# filmprocessor.net
KiCad netlist of a schematic drawn in EasyEDA Pro
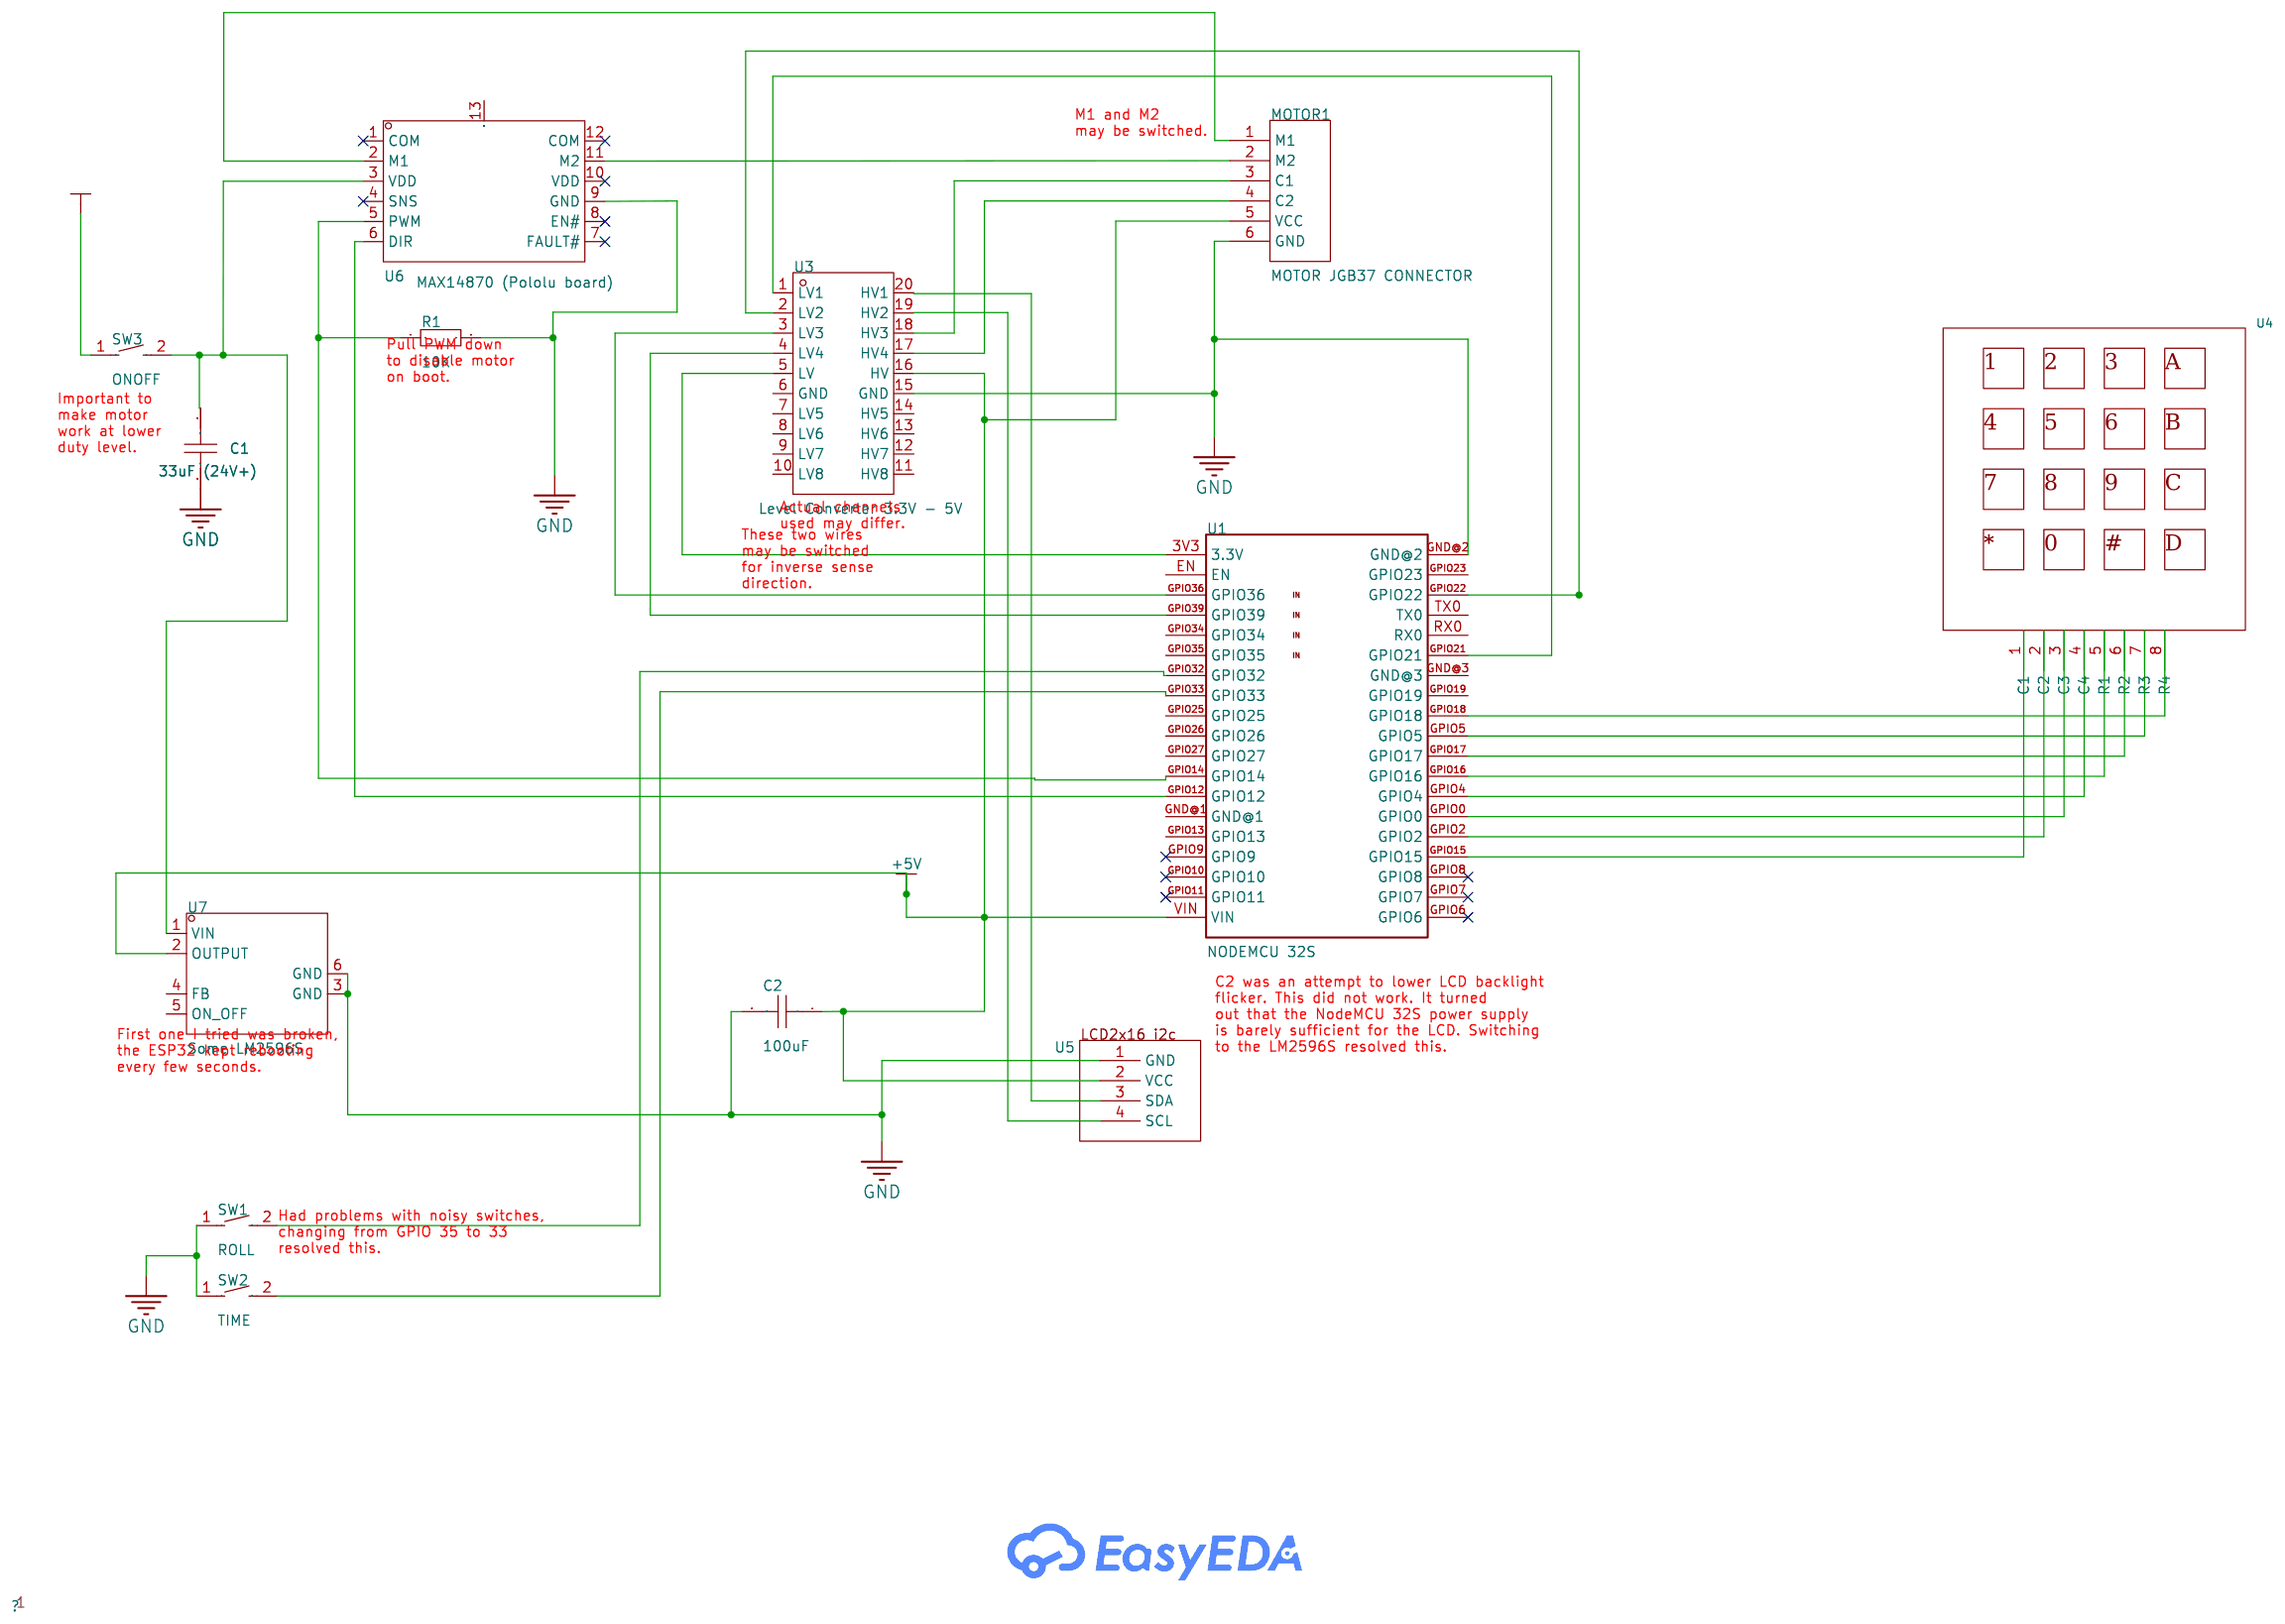
[diagram p0: schematic sheet]

(export (version "E")
  (design (tool "Eeschema 10.0.6"))
  (components
    (comp (ref "C1")
      (value "33uF (24V+)")
      (footprint "easyedapro:C0603")
      (libsource (lib "easyedapro") (part "CAP"))
    )
    (comp (ref "C2")
      (value "100uF")
      (footprint "easyedapro:C0603")
      (libsource (lib "easyedapro") (part "CAP"))
    )
    (comp (ref "MOTOR1")
      (value "MOTOR JGB37 CONNECTOR")
      (libsource (lib "easyedapro") (part "MOTOR JGB37 CONNECTOR"))
    )
    (comp (ref "R1") (value "10K") (footprint "easyedapro:R0603") (libsource (lib "easyedapro") (part "Res")))
    (comp (ref "SW1")
      (value "ROLL")
      (footprint "easyedapro:KEY-SMD_L6.0-W3.5-LS8.0")
      (libsource (lib "easyedapro") (part "BUTTON2,KEY"))
    )
    (comp (ref "SW2")
      (value "TIME")
      (footprint "easyedapro:KEY-SMD_L6.0-W3.5-LS8.0")
      (libsource (lib "easyedapro") (part "BUTTON2,KEY"))
    )
    (comp (ref "SW3")
      (value "ONOFF")
      (footprint "easyedapro:KEY-SMD_L6.0-W3.5-LS8.0")
      (libsource (lib "easyedapro") (part "BUTTON2,KEY"))
    )
    (comp (ref "U1")
      (value "NODEMCU32S")
      (footprint "easyedapro:footprints:NODEMCU32S")
      (libsource (lib "easyedapro") (part "NODEMCU32S_NODEMCU32S"))
    )
    (comp (ref "U3")
      (value "Level Converter 3.3V - 5V")
      (footprint "easyedapro:MPN-TH-20_L28.0-W14.0-P2.54-BL")
      (libsource (lib "easyedapro") (part "LEVEL CONVERTER 8"))
    )
    (comp (ref "U4") (value "~") (libsource (lib "easyedapro") (part "keypad")))
    (comp (ref "U5") (value "~") (libsource (lib "easyedapro") (part "lcd_2x16 with i2c module")))
    (comp (ref "U6")
      (value "MAX14870 (Pololu board)")
      (footprint "easyedapro:DFN-12_L3.0-W3.0-P0.50-LS3.0-BL-EP")
      (fields (field (name "Manufacturer") "ADI(亚德诺)/MAXIM(美信)"))
      (libsource (lib "easyedapro") (part "MAX14870ETC+T"))
    )
    (comp (ref "U7")
      (value "Some LM2596S")
      (footprint "easyedapro:TO-263-5_L10.4-W8.6-P1.70-LS15.3-BR")
      (libsource (lib "easyedapro") (part "LM2596S-ADJ_C3198435"))
    )
  )
  (nets
    (net (code "1") (name "+5V") (class "Default")
      (node (ref "C2") (pin "1") (pinfunction "1_1") (pintype "input"))
      (node (ref "MOTOR1") (pin "5") (pinfunction "VCC_5") (pintype "unspecified"))
      (node (ref "U1") (pin "VIN") (pinfunction "VIN_VIN") (pintype "bidirectional"))
      (node (ref "U3") (pin "16") (pinfunction "HV_16") (pintype "input"))
      (node (ref "U5") (pin "2") (pinfunction "VCC_2") (pintype "input"))
      (node (ref "U7") (pin "2") (pinfunction "OUTPUT_2") (pintype "unspecified"))
    )
    (net (code "2") (name "+24V") (class "Default")
      (node (ref "SW3") (pin "1") (pinfunction "1_1") (pintype "unspecified"))
    )
    (net (code "3") (name "GND") (class "Default")
      (node (ref "C1") (pin "2") (pinfunction "2_2") (pintype "input"))
      (node (ref "C2") (pin "2") (pinfunction "2_2") (pintype "input"))
      (node (ref "MOTOR1") (pin "6") (pinfunction "GND_6") (pintype "unspecified"))
      (node (ref "R1") (pin "2") (pinfunction "2_2") (pintype "input"))
      (node (ref "SW1") (pin "1") (pinfunction "1_1") (pintype "unspecified"))
      (node (ref "SW2") (pin "1") (pinfunction "1_1") (pintype "unspecified"))
      (node (ref "U1") (pin "GND@2") (pinfunction "GND@2_GND@2") (pintype "bidirectional"))
      (node (ref "U3") (pin "15") (pinfunction "GND_15") (pintype "input"))
      (node (ref "U5") (pin "1") (pinfunction "GND_1") (pintype "input"))
      (node (ref "U6") (pin "9") (pinfunction "GND_9") (pintype "unspecified"))
      (node (ref "U7") (pin "3") (pinfunction "GND_3") (pintype "unspecified"))
      (node (ref "U7") (pin "6") (pinfunction "GND_6") (pintype "unspecified"))
    )
    (net (code "4") (name "Net-(MOTOR1-C1)") (class "Default")
      (node (ref "MOTOR1") (pin "3") (pinfunction "C1_3") (pintype "unspecified"))
      (node (ref "U3") (pin "18") (pinfunction "HV3_18") (pintype "input"))
    )
    (net (code "5") (name "Net-(MOTOR1-C2)") (class "Default")
      (node (ref "MOTOR1") (pin "4") (pinfunction "C2_4") (pintype "unspecified"))
      (node (ref "U3") (pin "17") (pinfunction "HV4_17") (pintype "input"))
    )
    (net (code "6") (name "Net-(MOTOR1-M1)") (class "Default")
      (node (ref "MOTOR1") (pin "1") (pinfunction "M1_1") (pintype "unspecified"))
      (node (ref "U6") (pin "2") (pinfunction "M1_2") (pintype "unspecified"))
    )
    (net (code "7") (name "Net-(MOTOR1-M2)") (class "Default")
      (node (ref "MOTOR1") (pin "2") (pinfunction "M2_2") (pintype "unspecified"))
      (node (ref "U6") (pin "11") (pinfunction "M2_11") (pintype "unspecified"))
    )
    (net (code "8") (name "Net-(SW1-Pad2)") (class "Default")
      (node (ref "SW1") (pin "2") (pinfunction "2_2") (pintype "unspecified"))
      (node (ref "U1") (pin "GPIO32") (pinfunction "GPIO32_GPIO32") (pintype "bidirectional"))
    )
    (net (code "9") (name "Net-(SW2-Pad2)") (class "Default")
      (node (ref "SW2") (pin "2") (pinfunction "2_2") (pintype "unspecified"))
      (node (ref "U1") (pin "GPIO33") (pinfunction "GPIO33_GPIO33") (pintype "bidirectional"))
    )
    (net (code "10") (name "Net-(U1-3.3V)") (class "Default")
      (node (ref "U1") (pin "3V3") (pinfunction "3.3V_3V3") (pintype "bidirectional"))
      (node (ref "U3") (pin "5") (pinfunction "LV_5") (pintype "input"))
    )
    (net (code "11") (name "Net-(U3-HV1)") (class "Default")
      (node (ref "U3") (pin "20") (pinfunction "HV1_20") (pintype "input"))
      (node (ref "U5") (pin "3") (pinfunction "SDA_3") (pintype "input"))
    )
    (net (code "12") (name "Net-(U3-LV1)") (class "Default")
      (node (ref "U1") (pin "GPIO21") (pinfunction "GPIO21_GPIO21") (pintype "bidirectional"))
      (node (ref "U3") (pin "1") (pinfunction "LV1_1") (pintype "input"))
    )
    (net (code "13") (name "Net-(U3-LV2)") (class "Default")
      (node (ref "U1") (pin "GPIO22") (pinfunction "GPIO22_GPIO22") (pintype "bidirectional"))
      (node (ref "U3") (pin "2") (pinfunction "LV2_2") (pintype "input"))
    )
    (net (code "14") (name "Net-(U3-LV3)") (class "Default")
      (node (ref "U1") (pin "GPIO36") (pinfunction "GPIO36_GPIO36") (pintype "input"))
      (node (ref "U3") (pin "3") (pinfunction "LV3_3") (pintype "input"))
    )
    (net (code "15") (name "Net-(U3-LV4)") (class "Default")
      (node (ref "U1") (pin "GPIO39") (pinfunction "GPIO39_GPIO39") (pintype "input"))
      (node (ref "U3") (pin "4") (pinfunction "LV4_4") (pintype "input"))
    )
    (net (code "16") (name "Net-(U4-C1)") (class "Default")
      (node (ref "U1") (pin "GPIO15") (pinfunction "GPIO15_GPIO15") (pintype "bidirectional"))
      (node (ref "U4") (pin "1") (pinfunction "C1_1") (pintype "input"))
    )
    (net (code "17") (name "Net-(U4-C2)") (class "Default")
      (node (ref "U1") (pin "GPIO2") (pinfunction "GPIO2_GPIO2") (pintype "bidirectional"))
      (node (ref "U4") (pin "2") (pinfunction "C2_2") (pintype "input"))
    )
    (net (code "18") (name "Net-(U4-C3)") (class "Default")
      (node (ref "U1") (pin "GPIO0") (pinfunction "GPIO0_GPIO0") (pintype "bidirectional"))
      (node (ref "U4") (pin "3") (pinfunction "C3_3") (pintype "input"))
    )
    (net (code "19") (name "Net-(U4-C4)") (class "Default")
      (node (ref "U1") (pin "GPIO4") (pinfunction "GPIO4_GPIO4") (pintype "bidirectional"))
      (node (ref "U4") (pin "4") (pinfunction "C4_4") (pintype "input"))
    )
    (net (code "20") (name "Net-(U4-R1)") (class "Default")
      (node (ref "U1") (pin "GPIO16") (pinfunction "GPIO16_GPIO16") (pintype "bidirectional"))
      (node (ref "U4") (pin "5") (pinfunction "R1_5") (pintype "input"))
    )
    (net (code "21") (name "Net-(U4-R2)") (class "Default")
      (node (ref "U1") (pin "GPIO17") (pinfunction "GPIO17_GPIO17") (pintype "bidirectional"))
      (node (ref "U4") (pin "6") (pinfunction "R2_6") (pintype "input"))
    )
    (net (code "22") (name "Net-(U4-R3)") (class "Default")
      (node (ref "U1") (pin "GPIO5") (pinfunction "GPIO5_GPIO5") (pintype "bidirectional"))
      (node (ref "U4") (pin "7") (pinfunction "R3_7") (pintype "input"))
    )
    (net (code "23") (name "Net-(U4-R4)") (class "Default")
      (node (ref "U1") (pin "GPIO18") (pinfunction "GPIO18_GPIO18") (pintype "bidirectional"))
      (node (ref "U4") (pin "8") (pinfunction "R4_8") (pintype "input"))
    )
    (net (code "24") (name "Net-(U6-DIR)") (class "Default")
      (node (ref "U1") (pin "GPIO12") (pinfunction "GPIO12_GPIO12") (pintype "bidirectional"))
      (node (ref "U6") (pin "6") (pinfunction "DIR_6") (pintype "unspecified"))
    )
    (net (code "25") (name "Net-(U6-PWM)") (class "Default")
      (node (ref "R1") (pin "1") (pinfunction "1_1") (pintype "input"))
      (node (ref "U1") (pin "GPIO14") (pinfunction "GPIO14_GPIO14") (pintype "bidirectional"))
      (node (ref "U6") (pin "5") (pinfunction "PWM_5") (pintype "unspecified"))
    )
    (net (code "26") (name "Net-(U7-VIN)") (class "Default")
      (node (ref "C1") (pin "1") (pinfunction "1_1") (pintype "input"))
      (node (ref "SW3") (pin "2") (pinfunction "2_2") (pintype "unspecified"))
      (node (ref "U6") (pin "3") (pinfunction "VDD_3") (pintype "unspecified"))
      (node (ref "U7") (pin "1") (pinfunction "VIN_1") (pintype "unspecified"))
    )
    (net (code "27") (name "unconnected-(U1-PadEN)") (class "Default")
      (node (ref "U1") (pin "EN") (pinfunction "EN_EN") (pintype "bidirectional"))
    )
    (net (code "28") (name "unconnected-(U1-PadGND@1)") (class "Default")
      (node (ref "U1") (pin "GND@1") (pinfunction "GND@1_GND@1") (pintype "bidirectional"))
    )
    (net (code "29") (name "unconnected-(U1-PadGND@3)") (class "Default")
      (node (ref "U1") (pin "GND@3") (pinfunction "GND@3_GND@3") (pintype "bidirectional"))
    )
    (net (code "30") (name "unconnected-(U1-PadGPIO6)") (class "Default")
      (node (ref "U1") (pin "GPIO6") (pinfunction "GPIO6_GPIO6") (pintype "bidirectional+no_connect"))
    )
    (net (code "31") (name "unconnected-(U1-PadGPIO7)") (class "Default")
      (node (ref "U1") (pin "GPIO7") (pinfunction "GPIO7_GPIO7") (pintype "bidirectional+no_connect"))
    )
    (net (code "32") (name "unconnected-(U1-PadGPIO8)") (class "Default")
      (node (ref "U1") (pin "GPIO8") (pinfunction "GPIO8_GPIO8") (pintype "bidirectional+no_connect"))
    )
    (net (code "33") (name "unconnected-(U1-PadGPIO9)") (class "Default")
      (node (ref "U1") (pin "GPIO9") (pinfunction "GPIO9_GPIO9") (pintype "bidirectional+no_connect"))
    )
    (net (code "34") (name "unconnected-(U1-PadGPIO10)") (class "Default")
      (node (ref "U1") (pin "GPIO10") (pinfunction "GPIO10_GPIO10") (pintype "bidirectional+no_connect"))
    )
    (net (code "35") (name "unconnected-(U1-PadGPIO11)") (class "Default")
      (node (ref "U1") (pin "GPIO11") (pinfunction "GPIO11_GPIO11") (pintype "bidirectional+no_connect"))
    )
    (net (code "36") (name "unconnected-(U1-PadGPIO13)") (class "Default")
      (node (ref "U1") (pin "GPIO13") (pinfunction "GPIO13_GPIO13") (pintype "bidirectional"))
    )
    (net (code "37") (name "unconnected-(U1-PadGPIO19)") (class "Default")
      (node (ref "U1") (pin "GPIO19") (pinfunction "GPIO19_GPIO19") (pintype "bidirectional"))
    )
    (net (code "38") (name "unconnected-(U1-PadGPIO23)") (class "Default")
      (node (ref "U1") (pin "GPIO23") (pinfunction "GPIO23_GPIO23") (pintype "bidirectional"))
    )
    (net (code "39") (name "unconnected-(U1-PadGPIO25)") (class "Default")
      (node (ref "U1") (pin "GPIO25") (pinfunction "GPIO25_GPIO25") (pintype "bidirectional"))
    )
    (net (code "40") (name "unconnected-(U1-PadGPIO26)") (class "Default")
      (node (ref "U1") (pin "GPIO26") (pinfunction "GPIO26_GPIO26") (pintype "bidirectional"))
    )
    (net (code "41") (name "unconnected-(U1-PadGPIO27)") (class "Default")
      (node (ref "U1") (pin "GPIO27") (pinfunction "GPIO27_GPIO27") (pintype "bidirectional"))
    )
    (net (code "42") (name "unconnected-(U1-PadGPIO34)") (class "Default")
      (node (ref "U1") (pin "GPIO34") (pinfunction "GPIO34_GPIO34") (pintype "input"))
    )
    (net (code "43") (name "unconnected-(U1-PadGPIO35)") (class "Default")
      (node (ref "U1") (pin "GPIO35") (pinfunction "GPIO35_GPIO35") (pintype "input"))
    )
    (net (code "44") (name "unconnected-(U1-PadRX0)") (class "Default")
      (node (ref "U1") (pin "RX0") (pinfunction "RX0_RX0") (pintype "bidirectional"))
    )
    (net (code "45") (name "unconnected-(U1-PadTX0)") (class "Default")
      (node (ref "U1") (pin "TX0") (pinfunction "TX0_TX0") (pintype "bidirectional"))
    )
    (net (code "46") (name "unconnected-(U3-GND-Pad6)") (class "Default")
      (node (ref "U3") (pin "6") (pinfunction "GND_6") (pintype "input"))
    )
    (net (code "47") (name "unconnected-(U3-HV2-Pad19)") (class "Default")
      (node (ref "U3") (pin "19") (pinfunction "HV2_19") (pintype "input"))
    )
    (net (code "48") (name "unconnected-(U3-HV5-Pad14)") (class "Default")
      (node (ref "U3") (pin "14") (pinfunction "HV5_14") (pintype "input"))
    )
    (net (code "49") (name "unconnected-(U3-HV6-Pad13)") (class "Default")
      (node (ref "U3") (pin "13") (pinfunction "HV6_13") (pintype "input"))
    )
    (net (code "50") (name "unconnected-(U3-HV7-Pad12)") (class "Default")
      (node (ref "U3") (pin "12") (pinfunction "HV7_12") (pintype "input"))
    )
    (net (code "51") (name "unconnected-(U3-HV8-Pad11)") (class "Default")
      (node (ref "U3") (pin "11") (pinfunction "HV8_11") (pintype "input"))
    )
    (net (code "52") (name "unconnected-(U3-LV5-Pad7)") (class "Default")
      (node (ref "U3") (pin "7") (pinfunction "LV5_7") (pintype "input"))
    )
    (net (code "53") (name "unconnected-(U3-LV6-Pad8)") (class "Default")
      (node (ref "U3") (pin "8") (pinfunction "LV6_8") (pintype "input"))
    )
    (net (code "54") (name "unconnected-(U3-LV7-Pad9)") (class "Default")
      (node (ref "U3") (pin "9") (pinfunction "LV7_9") (pintype "input"))
    )
    (net (code "55") (name "unconnected-(U3-LV8-Pad10)") (class "Default")
      (node (ref "U3") (pin "10") (pinfunction "LV8_10") (pintype "input"))
    )
    (net (code "56") (name "unconnected-(U5-SCL-Pad4)") (class "Default")
      (node (ref "U5") (pin "4") (pinfunction "SCL_4") (pintype "input"))
    )
    (net (code "57") (name "unconnected-(U6-COM-Pad1)") (class "Default")
      (node (ref "U6") (pin "1") (pinfunction "COM_1") (pintype "unspecified+no_connect"))
    )
    (net (code "58") (name "unconnected-(U6-COM-Pad12)") (class "Default")
      (node (ref "U6") (pin "12") (pinfunction "COM_12") (pintype "unspecified+no_connect"))
    )
    (net (code "59") (name "unconnected-(U6-EN#-Pad8)") (class "Default")
      (node (ref "U6") (pin "8") (pinfunction "EN#_8") (pintype "unspecified+no_connect"))
    )
    (net (code "60") (name "unconnected-(U6-FAULT#-Pad7)") (class "Default")
      (node (ref "U6") (pin "7") (pinfunction "FAULT#_7") (pintype "unspecified+no_connect"))
    )
    (net (code "61") (name "unconnected-(U6-PAD-Pad13)") (class "Default")
      (node (ref "U6") (pin "13") (pinfunction "PAD_13") (pintype "unspecified"))
    )
    (net (code "62") (name "unconnected-(U6-SNS-Pad4)") (class "Default")
      (node (ref "U6") (pin "4") (pinfunction "SNS_4") (pintype "unspecified+no_connect"))
    )
    (net (code "63") (name "unconnected-(U6-VDD-Pad10)") (class "Default")
      (node (ref "U6") (pin "10") (pinfunction "VDD_10") (pintype "unspecified+no_connect"))
    )
    (net (code "64") (name "unconnected-(U7-FB-Pad4)") (class "Default")
      (node (ref "U7") (pin "4") (pinfunction "FB_4") (pintype "unspecified"))
    )
    (net (code "65") (name "unconnected-(U7-ON_OFF-Pad5)") (class "Default")
      (node (ref "U7") (pin "5") (pinfunction "ON_OFF_5") (pintype "unspecified"))
    )
  )
)
